# pot3elec.net
KiCad netlist of a schematic drawn in EAGLE
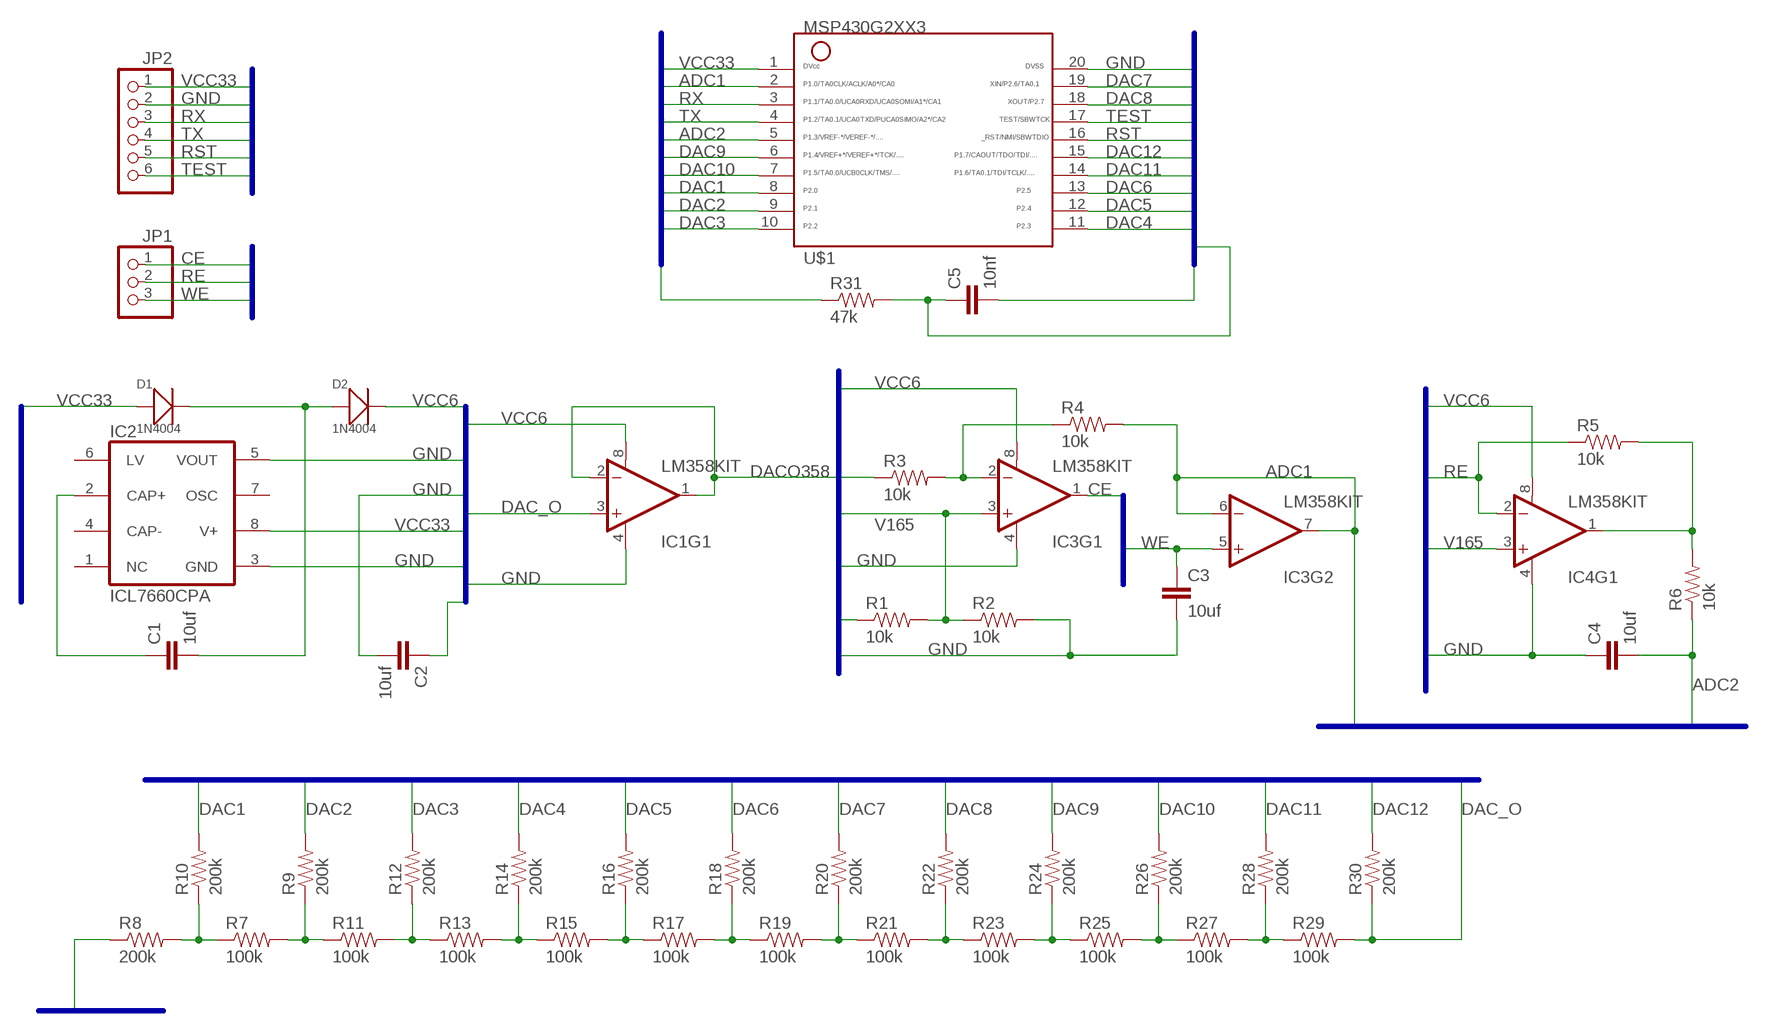
[diagram p0: schematic, sheet 1]

(export (version "E")
  (design (tool "Eeschema 10.0.6"))
  (components
    (comp (ref "C1")
      (value "10uf")
      (footprint "eagle-import:C2.5-3")
      (libsource (lib "eagle-import") (part "C2,5-3"))
    )
    (comp (ref "C2")
      (value "10uf")
      (footprint "eagle-import:C2.5-3")
      (libsource (lib "eagle-import") (part "C2,5-3"))
    )
    (comp (ref "C3")
      (value "10uf")
      (footprint "eagle-import:C2.5-3")
      (libsource (lib "eagle-import") (part "C2,5-3"))
    )
    (comp (ref "C4")
      (value "10uf")
      (footprint "eagle-import:C2.5-3")
      (libsource (lib "eagle-import") (part "C2,5-3"))
    )
    (comp (ref "C5")
      (value "10nf")
      (footprint "eagle-import:C2.5-3")
      (libsource (lib "eagle-import") (part "C2,5-3"))
    )
    (comp (ref "D1")
      (value "1N4004")
      (footprint "eagle-import:DO-41")
      (libsource (lib "eagle-import") (part "DIP-DIODE-400V-1A(DO-41)"))
    )
    (comp (ref "D2")
      (value "1N4004")
      (footprint "eagle-import:DO-41")
      (libsource (lib "eagle-import") (part "DIP-DIODE-400V-1A(DO-41)"))
    )
    (comp (ref "IC1")
      (value "LM358KIT")
      (footprint "eagle-import:DIP08-KIT")
      (libsource (lib "eagle-import") (part "LM358KIT"))
    )
    (comp (ref "IC2")
      (value "ICL7660CPA")
      (footprint "eagle-import:DIL08")
      (fields (field (name "MF") "INTERSIL"))
      (libsource (lib "eagle-import") (part "ICL7660CPA"))
    )
    (comp (ref "IC3")
      (value "LM358KIT")
      (footprint "eagle-import:DIP08-KIT")
      (libsource (lib "eagle-import") (part "LM358KIT"))
    )
    (comp (ref "IC4")
      (value "LM358KIT")
      (footprint "eagle-import:DIP08-KIT")
      (libsource (lib "eagle-import") (part "LM358KIT"))
    )
    (comp (ref "JP1")
      (value "PINHD-1X3")
      (footprint "eagle-import:1X03")
      (libsource (lib "eagle-import") (part "PINHD-1X3"))
    )
    (comp (ref "JP2")
      (value "PINHD-1X6")
      (footprint "eagle-import:1X06")
      (libsource (lib "eagle-import") (part "PINHD-1X6"))
    )
    (comp (ref "R1")
      (value "10k")
      (footprint "eagle-import:1206")
      (libsource (lib "eagle-import") (part "RESISTOR1206"))
    )
    (comp (ref "R2")
      (value "10k")
      (footprint "eagle-import:1206")
      (libsource (lib "eagle-import") (part "RESISTOR1206"))
    )
    (comp (ref "R3")
      (value "10k")
      (footprint "eagle-import:1206")
      (libsource (lib "eagle-import") (part "RESISTOR1206"))
    )
    (comp (ref "R4")
      (value "10k")
      (footprint "eagle-import:1206")
      (libsource (lib "eagle-import") (part "RESISTOR1206"))
    )
    (comp (ref "R5")
      (value "10k")
      (footprint "eagle-import:1206")
      (libsource (lib "eagle-import") (part "RESISTOR1206"))
    )
    (comp (ref "R6")
      (value "10k")
      (footprint "eagle-import:1206")
      (libsource (lib "eagle-import") (part "RESISTOR1206"))
    )
    (comp (ref "R7")
      (value "100k")
      (footprint "eagle-import:1206")
      (libsource (lib "eagle-import") (part "RESISTOR1206"))
    )
    (comp (ref "R8")
      (value "200k")
      (footprint "eagle-import:1206")
      (libsource (lib "eagle-import") (part "RESISTOR1206"))
    )
    (comp (ref "R9")
      (value "200k")
      (footprint "eagle-import:1206")
      (libsource (lib "eagle-import") (part "RESISTOR1206"))
    )
    (comp (ref "R10")
      (value "200k")
      (footprint "eagle-import:1206")
      (libsource (lib "eagle-import") (part "RESISTOR1206"))
    )
    (comp (ref "R11")
      (value "100k")
      (footprint "eagle-import:1206")
      (libsource (lib "eagle-import") (part "RESISTOR1206"))
    )
    (comp (ref "R12")
      (value "200k")
      (footprint "eagle-import:1206")
      (libsource (lib "eagle-import") (part "RESISTOR1206"))
    )
    (comp (ref "R13")
      (value "100k")
      (footprint "eagle-import:1206")
      (libsource (lib "eagle-import") (part "RESISTOR1206"))
    )
    (comp (ref "R14")
      (value "200k")
      (footprint "eagle-import:1206")
      (libsource (lib "eagle-import") (part "RESISTOR1206"))
    )
    (comp (ref "R15")
      (value "100k")
      (footprint "eagle-import:1206")
      (libsource (lib "eagle-import") (part "RESISTOR1206"))
    )
    (comp (ref "R16")
      (value "200k")
      (footprint "eagle-import:1206")
      (libsource (lib "eagle-import") (part "RESISTOR1206"))
    )
    (comp (ref "R17")
      (value "100k")
      (footprint "eagle-import:1206")
      (libsource (lib "eagle-import") (part "RESISTOR1206"))
    )
    (comp (ref "R18")
      (value "200k")
      (footprint "eagle-import:1206")
      (libsource (lib "eagle-import") (part "RESISTOR1206"))
    )
    (comp (ref "R19")
      (value "100k")
      (footprint "eagle-import:1206")
      (libsource (lib "eagle-import") (part "RESISTOR1206"))
    )
    (comp (ref "R20")
      (value "200k")
      (footprint "eagle-import:1206")
      (libsource (lib "eagle-import") (part "RESISTOR1206"))
    )
    (comp (ref "R21")
      (value "100k")
      (footprint "eagle-import:1206")
      (libsource (lib "eagle-import") (part "RESISTOR1206"))
    )
    (comp (ref "R22")
      (value "200k")
      (footprint "eagle-import:1206")
      (libsource (lib "eagle-import") (part "RESISTOR1206"))
    )
    (comp (ref "R23")
      (value "100k")
      (footprint "eagle-import:1206")
      (libsource (lib "eagle-import") (part "RESISTOR1206"))
    )
    (comp (ref "R24")
      (value "200k")
      (footprint "eagle-import:1206")
      (libsource (lib "eagle-import") (part "RESISTOR1206"))
    )
    (comp (ref "R25")
      (value "100k")
      (footprint "eagle-import:1206")
      (libsource (lib "eagle-import") (part "RESISTOR1206"))
    )
    (comp (ref "R26")
      (value "200k")
      (footprint "eagle-import:1206")
      (libsource (lib "eagle-import") (part "RESISTOR1206"))
    )
    (comp (ref "R27")
      (value "100k")
      (footprint "eagle-import:1206")
      (libsource (lib "eagle-import") (part "RESISTOR1206"))
    )
    (comp (ref "R28")
      (value "200k")
      (footprint "eagle-import:1206")
      (libsource (lib "eagle-import") (part "RESISTOR1206"))
    )
    (comp (ref "R29")
      (value "100k")
      (footprint "eagle-import:1206")
      (libsource (lib "eagle-import") (part "RESISTOR1206"))
    )
    (comp (ref "R30")
      (value "200k")
      (footprint "eagle-import:1206")
      (libsource (lib "eagle-import") (part "RESISTOR1206"))
    )
    (comp (ref "R31")
      (value "47k")
      (footprint "eagle-import:1206")
      (libsource (lib "eagle-import") (part "RESISTOR1206"))
    )
    (comp (ref "U$1")
      (value "G2XX3---N20")
      (footprint "eagle-import:N20")
      (libsource (lib "eagle-import") (part "G2XX3---N20"))
    )
  )
  (nets
    (net (code "1") (name "/ADC1") (class "Default")
      (node (ref "IC3") (pin "6") (pinfunction "-IN_6") (pintype "input"))
      (node (ref "IC3") (pin "7") (pinfunction "OUT_7") (pintype "output"))
      (node (ref "R4") (pin "2") (pinfunction "2_2") (pintype "passive"))
      (node (ref "U$1") (pin "2") (pinfunction "2_2") (pintype "bidirectional"))
    )
    (net (code "2") (name "/ADC2") (class "Default")
      (node (ref "C4") (pin "2") (pinfunction "2_2") (pintype "passive"))
      (node (ref "R6") (pin "1") (pinfunction "1_1") (pintype "passive"))
      (node (ref "U$1") (pin "5") (pinfunction "5_5") (pintype "bidirectional"))
    )
    (net (code "3") (name "/CE") (class "Default")
      (node (ref "IC3") (pin "1") (pinfunction "OUT_1") (pintype "output"))
      (node (ref "JP1") (pin "1") (pinfunction "1_1") (pintype "passive"))
    )
    (net (code "4") (name "/DAC1") (class "Default")
      (node (ref "R10") (pin "2") (pinfunction "2_2") (pintype "passive"))
      (node (ref "U$1") (pin "8") (pinfunction "8_8") (pintype "bidirectional"))
    )
    (net (code "5") (name "/DAC2") (class "Default")
      (node (ref "R9") (pin "2") (pinfunction "2_2") (pintype "passive"))
      (node (ref "U$1") (pin "9") (pinfunction "9_9") (pintype "bidirectional"))
    )
    (net (code "6") (name "/DAC3") (class "Default")
      (node (ref "R12") (pin "2") (pinfunction "2_2") (pintype "passive"))
      (node (ref "U$1") (pin "10") (pinfunction "10_10") (pintype "bidirectional"))
    )
    (net (code "7") (name "/DAC4") (class "Default")
      (node (ref "R14") (pin "2") (pinfunction "2_2") (pintype "passive"))
      (node (ref "U$1") (pin "11") (pinfunction "11_11") (pintype "bidirectional"))
    )
    (net (code "8") (name "/DAC5") (class "Default")
      (node (ref "R16") (pin "2") (pinfunction "2_2") (pintype "passive"))
      (node (ref "U$1") (pin "12") (pinfunction "12_12") (pintype "bidirectional"))
    )
    (net (code "9") (name "/DAC6") (class "Default")
      (node (ref "R18") (pin "2") (pinfunction "2_2") (pintype "passive"))
      (node (ref "U$1") (pin "13") (pinfunction "13_13") (pintype "bidirectional"))
    )
    (net (code "10") (name "/DAC7") (class "Default")
      (node (ref "R20") (pin "2") (pinfunction "2_2") (pintype "passive"))
      (node (ref "U$1") (pin "19") (pinfunction "19_19") (pintype "bidirectional"))
    )
    (net (code "11") (name "/DAC8") (class "Default")
      (node (ref "R22") (pin "2") (pinfunction "2_2") (pintype "passive"))
      (node (ref "U$1") (pin "18") (pinfunction "18_18") (pintype "bidirectional"))
    )
    (net (code "12") (name "/DAC9") (class "Default")
      (node (ref "R24") (pin "2") (pinfunction "2_2") (pintype "passive"))
      (node (ref "U$1") (pin "6") (pinfunction "6_6") (pintype "bidirectional"))
    )
    (net (code "13") (name "/DAC10") (class "Default")
      (node (ref "R26") (pin "2") (pinfunction "2_2") (pintype "passive"))
      (node (ref "U$1") (pin "7") (pinfunction "7_7") (pintype "bidirectional"))
    )
    (net (code "14") (name "/DAC11") (class "Default")
      (node (ref "R28") (pin "2") (pinfunction "2_2") (pintype "passive"))
      (node (ref "U$1") (pin "14") (pinfunction "14_14") (pintype "bidirectional"))
    )
    (net (code "15") (name "/DAC12") (class "Default")
      (node (ref "R30") (pin "2") (pinfunction "2_2") (pintype "passive"))
      (node (ref "U$1") (pin "15") (pinfunction "15_15") (pintype "bidirectional"))
    )
    (net (code "16") (name "/DACO358") (class "Default")
      (node (ref "IC1") (pin "1") (pinfunction "OUT_1") (pintype "output"))
      (node (ref "IC1") (pin "2") (pinfunction "-IN_2") (pintype "input"))
      (node (ref "R3") (pin "1") (pinfunction "1_1") (pintype "passive"))
    )
    (net (code "17") (name "/DAC_O") (class "Default")
      (node (ref "IC1") (pin "3") (pinfunction "+IN_3") (pintype "input"))
      (node (ref "R29") (pin "2") (pinfunction "2_2") (pintype "passive"))
      (node (ref "R30") (pin "1") (pinfunction "1_1") (pintype "passive"))
    )
    (net (code "18") (name "/GND") (class "Default")
      (node (ref "C2") (pin "2") (pinfunction "2_2") (pintype "passive"))
      (node (ref "C3") (pin "2") (pinfunction "2_2") (pintype "passive"))
      (node (ref "C4") (pin "1") (pinfunction "1_1") (pintype "passive"))
      (node (ref "C5") (pin "2") (pinfunction "2_2") (pintype "passive"))
      (node (ref "IC1") (pin "4") (pinfunction "V-_4") (pintype "power_in"))
      (node (ref "IC2") (pin "3") (pinfunction "GND_3") (pintype "power_in"))
      (node (ref "IC2") (pin "5") (pinfunction "VOUT_5") (pintype "output"))
      (node (ref "IC3") (pin "4") (pinfunction "V-_4") (pintype "power_in"))
      (node (ref "IC4") (pin "4") (pinfunction "V-_4") (pintype "power_in"))
      (node (ref "JP2") (pin "2") (pinfunction "2_2") (pintype "passive"))
      (node (ref "R2") (pin "2") (pinfunction "2_2") (pintype "passive"))
      (node (ref "R8") (pin "1") (pinfunction "1_1") (pintype "passive"))
      (node (ref "U$1") (pin "20") (pinfunction "20_20") (pintype "bidirectional"))
    )
    (net (code "19") (name "/RE") (class "Default")
      (node (ref "IC4") (pin "2") (pinfunction "-IN_2") (pintype "input"))
      (node (ref "JP1") (pin "2") (pinfunction "2_2") (pintype "passive"))
      (node (ref "R5") (pin "1") (pinfunction "1_1") (pintype "passive"))
    )
    (net (code "20") (name "/RST") (class "Default")
      (node (ref "C5") (pin "1") (pinfunction "1_1") (pintype "passive"))
      (node (ref "JP2") (pin "5") (pinfunction "5_5") (pintype "passive"))
      (node (ref "R31") (pin "2") (pinfunction "2_2") (pintype "passive"))
      (node (ref "U$1") (pin "16") (pinfunction "16_16") (pintype "bidirectional"))
    )
    (net (code "21") (name "/RX") (class "Default")
      (node (ref "JP2") (pin "3") (pinfunction "3_3") (pintype "passive"))
      (node (ref "U$1") (pin "3") (pinfunction "3_3") (pintype "bidirectional"))
    )
    (net (code "22") (name "/TEST") (class "Default")
      (node (ref "JP2") (pin "6") (pinfunction "6_6") (pintype "passive"))
      (node (ref "U$1") (pin "17") (pinfunction "17_17") (pintype "bidirectional"))
    )
    (net (code "23") (name "/TX") (class "Default")
      (node (ref "JP2") (pin "4") (pinfunction "4_4") (pintype "passive"))
      (node (ref "U$1") (pin "4") (pinfunction "4_4") (pintype "bidirectional"))
    )
    (net (code "24") (name "/V165") (class "Default")
      (node (ref "IC3") (pin "3") (pinfunction "+IN_3") (pintype "input"))
      (node (ref "IC4") (pin "3") (pinfunction "+IN_3") (pintype "input"))
      (node (ref "R1") (pin "2") (pinfunction "2_2") (pintype "passive"))
      (node (ref "R2") (pin "1") (pinfunction "1_1") (pintype "passive"))
    )
    (net (code "25") (name "/VCC6") (class "Default")
      (node (ref "C2") (pin "1") (pinfunction "1_1") (pintype "passive"))
      (node (ref "D2") (pin "2") (pinfunction "-_2") (pintype "passive"))
      (node (ref "IC1") (pin "8") (pinfunction "V+_8") (pintype "power_in"))
      (node (ref "IC3") (pin "8") (pinfunction "V+_8") (pintype "power_in"))
      (node (ref "IC4") (pin "8") (pinfunction "V+_8") (pintype "power_in"))
    )
    (net (code "26") (name "/VCC33") (class "Default")
      (node (ref "D1") (pin "1") (pinfunction "+_1") (pintype "passive"))
      (node (ref "IC2") (pin "8") (pinfunction "V+_8") (pintype "power_in"))
      (node (ref "JP2") (pin "1") (pinfunction "1_1") (pintype "passive"))
      (node (ref "R1") (pin "1") (pinfunction "1_1") (pintype "passive"))
      (node (ref "R31") (pin "1") (pinfunction "1_1") (pintype "passive"))
      (node (ref "U$1") (pin "1") (pinfunction "1_1") (pintype "bidirectional"))
    )
    (net (code "27") (name "/WE") (class "Default")
      (node (ref "C3") (pin "1") (pinfunction "1_1") (pintype "passive"))
      (node (ref "IC3") (pin "5") (pinfunction "+IN_5") (pintype "input"))
      (node (ref "JP1") (pin "3") (pinfunction "3_3") (pintype "passive"))
    )
    (net (code "31") (name "Net-(D1--)") (class "Default")
      (node (ref "C1") (pin "2") (pinfunction "2_2") (pintype "passive"))
      (node (ref "D1") (pin "2") (pinfunction "-_2") (pintype "passive"))
      (node (ref "D2") (pin "1") (pinfunction "+_1") (pintype "passive"))
    )
    (net (code "32") (name "Net-(IC2-CAP+)") (class "Default")
      (node (ref "C1") (pin "1") (pinfunction "1_1") (pintype "passive"))
      (node (ref "IC2") (pin "2") (pinfunction "CAP+_2") (pintype "passive"))
    )
    (net (code "33") (name "Net-(IC3A--IN)") (class "Default")
      (node (ref "IC3") (pin "2") (pinfunction "-IN_2") (pintype "input"))
      (node (ref "R3") (pin "2") (pinfunction "2_2") (pintype "passive"))
      (node (ref "R4") (pin "1") (pinfunction "1_1") (pintype "passive"))
    )
    (net (code "34") (name "Net-(IC4A-OUT)") (class "Default")
      (node (ref "IC4") (pin "1") (pinfunction "OUT_1") (pintype "output"))
      (node (ref "R5") (pin "2") (pinfunction "2_2") (pintype "passive"))
      (node (ref "R6") (pin "2") (pinfunction "2_2") (pintype "passive"))
    )
    (net (code "35") (name "Net-(R10-Pad1)") (class "Default")
      (node (ref "R10") (pin "1") (pinfunction "1_1") (pintype "passive"))
      (node (ref "R7") (pin "1") (pinfunction "1_1") (pintype "passive"))
      (node (ref "R8") (pin "2") (pinfunction "2_2") (pintype "passive"))
    )
    (net (code "36") (name "Net-(R11-Pad1)") (class "Default")
      (node (ref "R11") (pin "1") (pinfunction "1_1") (pintype "passive"))
      (node (ref "R7") (pin "2") (pinfunction "2_2") (pintype "passive"))
      (node (ref "R9") (pin "1") (pinfunction "1_1") (pintype "passive"))
    )
    (net (code "37") (name "Net-(R11-Pad2)") (class "Default")
      (node (ref "R11") (pin "2") (pinfunction "2_2") (pintype "passive"))
      (node (ref "R12") (pin "1") (pinfunction "1_1") (pintype "passive"))
      (node (ref "R13") (pin "1") (pinfunction "1_1") (pintype "passive"))
    )
    (net (code "38") (name "Net-(R13-Pad2)") (class "Default")
      (node (ref "R13") (pin "2") (pinfunction "2_2") (pintype "passive"))
      (node (ref "R14") (pin "1") (pinfunction "1_1") (pintype "passive"))
      (node (ref "R15") (pin "1") (pinfunction "1_1") (pintype "passive"))
    )
    (net (code "39") (name "Net-(R15-Pad2)") (class "Default")
      (node (ref "R15") (pin "2") (pinfunction "2_2") (pintype "passive"))
      (node (ref "R16") (pin "1") (pinfunction "1_1") (pintype "passive"))
      (node (ref "R17") (pin "1") (pinfunction "1_1") (pintype "passive"))
    )
    (net (code "40") (name "Net-(R17-Pad2)") (class "Default")
      (node (ref "R17") (pin "2") (pinfunction "2_2") (pintype "passive"))
      (node (ref "R18") (pin "1") (pinfunction "1_1") (pintype "passive"))
      (node (ref "R19") (pin "1") (pinfunction "1_1") (pintype "passive"))
    )
    (net (code "41") (name "Net-(R19-Pad2)") (class "Default")
      (node (ref "R19") (pin "2") (pinfunction "2_2") (pintype "passive"))
      (node (ref "R20") (pin "1") (pinfunction "1_1") (pintype "passive"))
      (node (ref "R21") (pin "1") (pinfunction "1_1") (pintype "passive"))
    )
    (net (code "42") (name "Net-(R21-Pad2)") (class "Default")
      (node (ref "R21") (pin "2") (pinfunction "2_2") (pintype "passive"))
      (node (ref "R22") (pin "1") (pinfunction "1_1") (pintype "passive"))
      (node (ref "R23") (pin "1") (pinfunction "1_1") (pintype "passive"))
    )
    (net (code "43") (name "Net-(R23-Pad2)") (class "Default")
      (node (ref "R23") (pin "2") (pinfunction "2_2") (pintype "passive"))
      (node (ref "R24") (pin "1") (pinfunction "1_1") (pintype "passive"))
      (node (ref "R25") (pin "1") (pinfunction "1_1") (pintype "passive"))
    )
    (net (code "44") (name "Net-(R25-Pad2)") (class "Default")
      (node (ref "R25") (pin "2") (pinfunction "2_2") (pintype "passive"))
      (node (ref "R26") (pin "1") (pinfunction "1_1") (pintype "passive"))
      (node (ref "R27") (pin "1") (pinfunction "1_1") (pintype "passive"))
    )
    (net (code "45") (name "Net-(R27-Pad2)") (class "Default")
      (node (ref "R27") (pin "2") (pinfunction "2_2") (pintype "passive"))
      (node (ref "R28") (pin "1") (pinfunction "1_1") (pintype "passive"))
      (node (ref "R29") (pin "1") (pinfunction "1_1") (pintype "passive"))
    )
    (net (code "46") (name "unconnected-(IC2-CAP--Pad4)") (class "Default")
      (node (ref "IC2") (pin "4") (pinfunction "CAP-_4") (pintype "passive"))
    )
    (net (code "47") (name "unconnected-(IC2-LV-Pad6)") (class "Default")
      (node (ref "IC2") (pin "6") (pinfunction "LV_6") (pintype "passive"))
    )
    (net (code "48") (name "unconnected-(IC2-NC-Pad1)") (class "Default")
      (node (ref "IC2") (pin "1") (pinfunction "NC_1") (pintype "no_connect"))
    )
    (net (code "49") (name "unconnected-(IC2-OSC-Pad7)") (class "Default")
      (node (ref "IC2") (pin "7") (pinfunction "OSC_7") (pintype "output"))
    )
  )
)
